# Photon_Sample.net
KiCad netlist of a schematic drawn in EAGLE
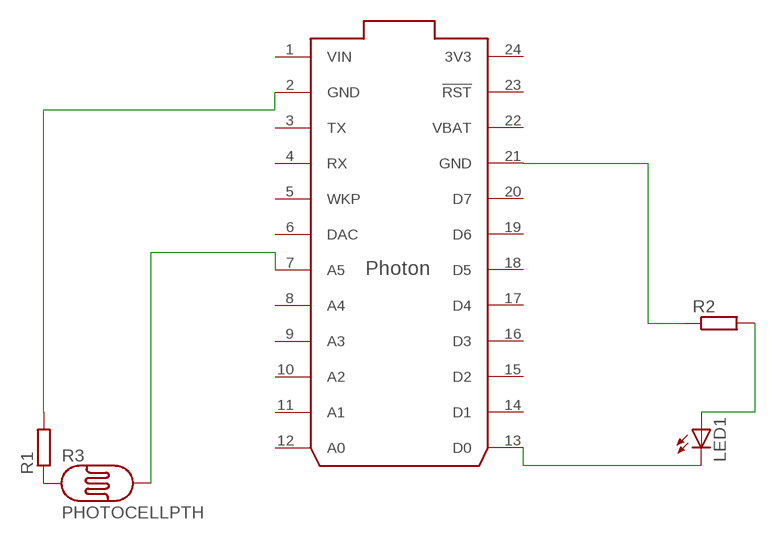
[diagram p0: schematic, sheet 1]

(export (version "E")
  (design (tool "Eeschema 10.0.6"))
  (components
    (comp (ref "LED1")
      (value "LED5MM")
      (footprint "eagle-import:LED5MM")
      (libsource (lib "eagle-import") (part "LED5MM"))
    )
    (comp (ref "R1")
      (value "R-EU_0309/12")
      (footprint "eagle-import:0309_12")
      (libsource (lib "eagle-import") (part "R-EU_0309/12"))
    )
    (comp (ref "R2")
      (value "R-EU_0309/12")
      (footprint "eagle-import:0309_12")
      (libsource (lib "eagle-import") (part "R-EU_0309/12"))
    )
    (comp (ref "R3")
      (value "PHOTOCELLPTH")
      (footprint "eagle-import:PHOTOCELL")
      (libsource (lib "eagle-import") (part "PHOTOCELLPTH"))
    )
    (comp (ref "U$1")
      (value "PHOTON_WITH_HEADERS")
      (footprint "eagle-import:PHOTON")
      (libsource (lib "eagle-import") (part "PHOTON_WITH_HEADERS"))
    )
  )
  (nets
    (net (code "1") (name "/3V3") (class "Default")
      (node (ref "U$1") (pin "24") (pinfunction "3V3_24") (pintype "power_in"))
    )
    (net (code "2") (name "/VBAT") (class "Default")
      (node (ref "U$1") (pin "22") (pinfunction "VBAT_22") (pintype "power_in"))
    )
    (net (code "3") (name "/VIN") (class "Default")
      (node (ref "U$1") (pin "1") (pinfunction "VIN_1") (pintype "power_in"))
    )
    (net (code "4") (name "Net-(LED1-C)") (class "Default")
      (node (ref "LED1") (pin "K") (pinfunction "C_K") (pintype "passive"))
      (node (ref "U$1") (pin "13") (pinfunction "D0_13") (pintype "bidirectional"))
    )
    (net (code "5") (name "Net-(LED1-PadA)") (class "Default")
      (node (ref "LED1") (pin "A") (pinfunction "A_A") (pintype "passive"))
      (node (ref "R2") (pin "2") (pinfunction "2_2") (pintype "passive"))
    )
    (net (code "6") (name "Net-(R1-Pad2)") (class "Default")
      (node (ref "R1") (pin "2") (pinfunction "2_2") (pintype "passive"))
      (node (ref "U$1") (pin "2") (pinfunction "GND_2") (pintype "power_in"))
    )
    (net (code "7") (name "Net-(R2-Pad1)") (class "Default")
      (node (ref "R2") (pin "1") (pinfunction "1_1") (pintype "passive"))
      (node (ref "U$1") (pin "21") (pinfunction "GND_21") (pintype "power_in"))
    )
    (net (code "8") (name "Net-(R3-P$1)") (class "Default")
      (node (ref "R1") (pin "1") (pinfunction "1_1") (pintype "passive"))
      (node (ref "R3") (pin "1") (pinfunction "P$1_1") (pintype "bidirectional"))
    )
    (net (code "9") (name "Net-(R3-P$2)") (class "Default")
      (node (ref "R3") (pin "2") (pinfunction "P$2_2") (pintype "bidirectional"))
      (node (ref "U$1") (pin "7") (pinfunction "A5_7") (pintype "bidirectional"))
    )
    (net (code "10") (name "unconnected-(U$1-A0-Pad12)") (class "Default")
      (node (ref "U$1") (pin "12") (pinfunction "A0_12") (pintype "bidirectional"))
    )
    (net (code "11") (name "unconnected-(U$1-A1-Pad11)") (class "Default")
      (node (ref "U$1") (pin "11") (pinfunction "A1_11") (pintype "bidirectional"))
    )
    (net (code "12") (name "unconnected-(U$1-A2-Pad10)") (class "Default")
      (node (ref "U$1") (pin "10") (pinfunction "A2_10") (pintype "bidirectional"))
    )
    (net (code "13") (name "unconnected-(U$1-A3-Pad9)") (class "Default")
      (node (ref "U$1") (pin "9") (pinfunction "A3_9") (pintype "bidirectional"))
    )
    (net (code "14") (name "unconnected-(U$1-A4-Pad8)") (class "Default")
      (node (ref "U$1") (pin "8") (pinfunction "A4_8") (pintype "bidirectional"))
    )
    (net (code "15") (name "unconnected-(U$1-D1-Pad14)") (class "Default")
      (node (ref "U$1") (pin "14") (pinfunction "D1_14") (pintype "bidirectional"))
    )
    (net (code "16") (name "unconnected-(U$1-D2-Pad15)") (class "Default")
      (node (ref "U$1") (pin "15") (pinfunction "D2_15") (pintype "bidirectional"))
    )
    (net (code "17") (name "unconnected-(U$1-D3-Pad16)") (class "Default")
      (node (ref "U$1") (pin "16") (pinfunction "D3_16") (pintype "bidirectional"))
    )
    (net (code "18") (name "unconnected-(U$1-D4-Pad17)") (class "Default")
      (node (ref "U$1") (pin "17") (pinfunction "D4_17") (pintype "bidirectional"))
    )
    (net (code "19") (name "unconnected-(U$1-D5-Pad18)") (class "Default")
      (node (ref "U$1") (pin "18") (pinfunction "D5_18") (pintype "bidirectional"))
    )
    (net (code "20") (name "unconnected-(U$1-D6-Pad19)") (class "Default")
      (node (ref "U$1") (pin "19") (pinfunction "D6_19") (pintype "bidirectional"))
    )
    (net (code "21") (name "unconnected-(U$1-D7-Pad20)") (class "Default")
      (node (ref "U$1") (pin "20") (pinfunction "D7_20") (pintype "bidirectional"))
    )
    (net (code "22") (name "unconnected-(U$1-DAC-Pad6)") (class "Default")
      (node (ref "U$1") (pin "6") (pinfunction "DAC_6") (pintype "bidirectional"))
    )
    (net (code "23") (name "unconnected-(U$1-RX-Pad4)") (class "Default")
      (node (ref "U$1") (pin "4") (pinfunction "RX_4") (pintype "bidirectional"))
    )
    (net (code "24") (name "unconnected-(U$1-TX-Pad3)") (class "Default")
      (node (ref "U$1") (pin "3") (pinfunction "TX_3") (pintype "bidirectional"))
    )
    (net (code "25") (name "unconnected-(U$1-WKP-Pad5)") (class "Default")
      (node (ref "U$1") (pin "5") (pinfunction "WKP_5") (pintype "bidirectional"))
    )
    (net (code "26") (name "unconnected-(U$1-~{RST}-Pad23)") (class "Default")
      (node (ref "U$1") (pin "23") (pinfunction "~{RST}_23") (pintype "bidirectional"))
    )
  )
)
